# MCU.net
KiCad netlist of a schematic drawn in Altium Designer
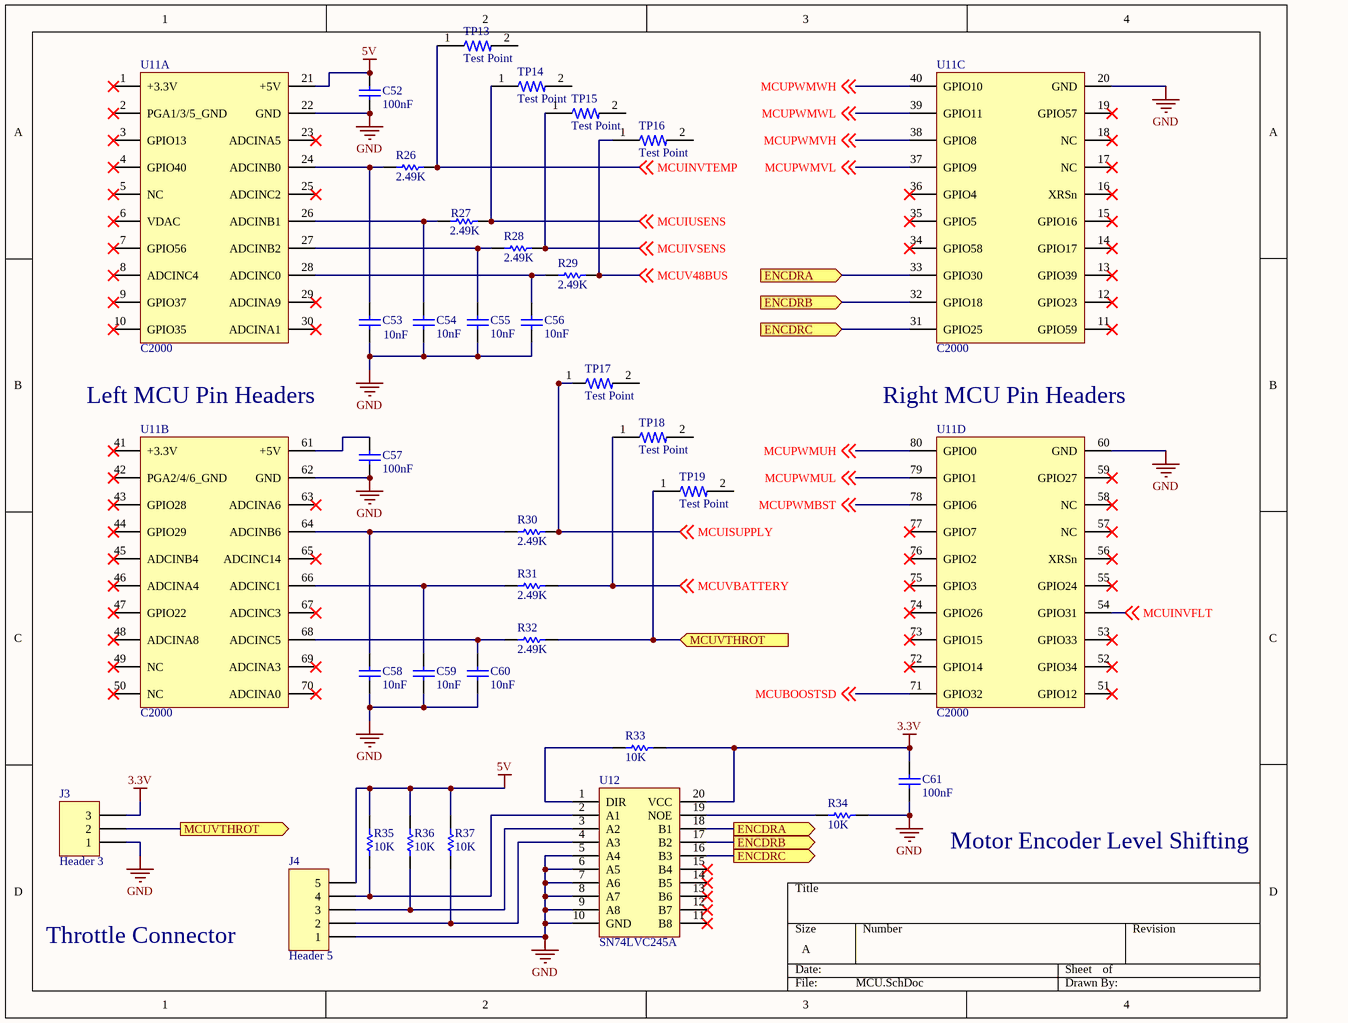
[diagram p0: MCU.SchDoc]

(export (version "E")
  (design (tool "Eeschema 10.0.6"))
  (components
    (comp (ref "C52")
      (value "100nF")
      (footprint "CAPC1609X100X15LL20")
      (fields
        (field (name "MANUFACTURER") "AVX Interconnect / Elco")
        (field (name "PART NUMBER") "TACL105M006XTA")
      )
      (libsource (lib "Altium Content Vault") (part "CAP"))
    )
    (comp (ref "C53")
      (value "10nF")
      (footprint "CAPC1609X100X15LL20")
      (fields
        (field (name "MANUFACTURER") "AVX Interconnect / Elco")
        (field (name "PART NUMBER") "TACL105M006XTA")
      )
      (libsource (lib "Altium Content Vault") (part "CAP"))
    )
    (comp (ref "C54")
      (value "10nF")
      (footprint "CAPC1609X100X15LL20")
      (fields
        (field (name "MANUFACTURER") "AVX Interconnect / Elco")
        (field (name "PART NUMBER") "TACL105M006XTA")
      )
      (libsource (lib "Altium Content Vault") (part "CAP"))
    )
    (comp (ref "C55")
      (value "10nF")
      (footprint "CAPC1609X100X15LL20")
      (fields
        (field (name "MANUFACTURER") "AVX Interconnect / Elco")
        (field (name "PART NUMBER") "TACL105M006XTA")
      )
      (libsource (lib "Altium Content Vault") (part "CAP"))
    )
    (comp (ref "C56")
      (value "10nF")
      (footprint "CAPC1609X100X15LL20")
      (fields
        (field (name "MANUFACTURER") "AVX Interconnect / Elco")
        (field (name "PART NUMBER") "TACL105M006XTA")
      )
      (libsource (lib "Altium Content Vault") (part "CAP"))
    )
    (comp (ref "C57")
      (value "100nF")
      (footprint "CAPC1609X100X15LL20")
      (fields
        (field (name "MANUFACTURER") "AVX Interconnect / Elco")
        (field (name "PART NUMBER") "TACL105M006XTA")
      )
      (libsource (lib "Altium Content Vault") (part "CAP"))
    )
    (comp (ref "C58")
      (value "10nF")
      (footprint "CAPC1609X100X15LL20")
      (fields
        (field (name "MANUFACTURER") "AVX Interconnect / Elco")
        (field (name "PART NUMBER") "TACL105M006XTA")
      )
      (libsource (lib "Altium Content Vault") (part "CAP"))
    )
    (comp (ref "C59")
      (value "10nF")
      (footprint "CAPC1609X100X15LL20")
      (fields
        (field (name "MANUFACTURER") "AVX Interconnect / Elco")
        (field (name "PART NUMBER") "TACL105M006XTA")
      )
      (libsource (lib "Altium Content Vault") (part "CAP"))
    )
    (comp (ref "C60")
      (value "10nF")
      (footprint "CAPC1609X100X15LL20")
      (fields
        (field (name "MANUFACTURER") "AVX Interconnect / Elco")
        (field (name "PART NUMBER") "TACL105M006XTA")
      )
      (libsource (lib "Altium Content Vault") (part "CAP"))
    )
    (comp (ref "C61")
      (value "100nF")
      (footprint "CAPC1609X100X15LL20")
      (fields
        (field (name "MANUFACTURER") "AVX Interconnect / Elco")
        (field (name "PART NUMBER") "TACL105M006XTA")
      )
      (libsource (lib "Altium Content Vault") (part "CAP"))
    )
    (comp (ref "J3")
      (value "Header 3")
      (footprint "3-Pin TB 5mm Pitch")
      (description "Header, 3-Pin")
      (fields (field (name "PUBLISHER") "Altium Limited"))
      (libsource (lib "Miscellaneous Connectors") (part "Header 3"))
    )
    (comp (ref "J4")
      (value "Header 5")
      (footprint "5-Pin TB 5mm Pitch")
      (description "Header, 5-Pin")
      (fields (field (name "PUBLISHER") "Altium Limited"))
      (libsource (lib "Miscellaneous Connectors") (part "Header 5"))
    )
    (comp (ref "R26")
      (value "2.49K")
      (footprint "RESC1609X50X30NL8T20")
      (description "Chip Resistor, 0 Ohm, Jumper, 100 mW, -55 to 155 degC, 0603 (1608 Metric), RoHS, Tape and Reel")
      (fields (field (name "MANUFACTURER") "Vishay Semiconductor"))
      (libsource (lib "Altium Content Vault") (part "RES-2"))
    )
    (comp (ref "R27")
      (value "2.49K")
      (footprint "RESC1609X50X30NL8T20")
      (description "Chip Resistor, 0 Ohm, Jumper, 100 mW, -55 to 155 degC, 0603 (1608 Metric), RoHS, Tape and Reel")
      (fields (field (name "MANUFACTURER") "Vishay Semiconductor"))
      (libsource (lib "Altium Content Vault") (part "RES-2"))
    )
    (comp (ref "R28")
      (value "2.49K")
      (footprint "RESC1609X50X30NL8T20")
      (description "Chip Resistor, 0 Ohm, Jumper, 100 mW, -55 to 155 degC, 0603 (1608 Metric), RoHS, Tape and Reel")
      (fields (field (name "MANUFACTURER") "Vishay Semiconductor"))
      (libsource (lib "Altium Content Vault") (part "RES-2"))
    )
    (comp (ref "R29")
      (value "2.49K")
      (footprint "RESC1609X50X30NL8T20")
      (description "Chip Resistor, 0 Ohm, Jumper, 100 mW, -55 to 155 degC, 0603 (1608 Metric), RoHS, Tape and Reel")
      (fields (field (name "MANUFACTURER") "Vishay Semiconductor"))
      (libsource (lib "Altium Content Vault") (part "RES-2"))
    )
    (comp (ref "R30")
      (value "2.49K")
      (footprint "RESC1609X50X30NL8T20")
      (description "Chip Resistor, 0 Ohm, Jumper, 100 mW, -55 to 155 degC, 0603 (1608 Metric), RoHS, Tape and Reel")
      (fields (field (name "MANUFACTURER") "Vishay Semiconductor"))
      (libsource (lib "Altium Content Vault") (part "RES-2"))
    )
    (comp (ref "R31")
      (value "2.49K")
      (footprint "RESC1609X50X30NL8T20")
      (description "Chip Resistor, 0 Ohm, Jumper, 100 mW, -55 to 155 degC, 0603 (1608 Metric), RoHS, Tape and Reel")
      (fields (field (name "MANUFACTURER") "Vishay Semiconductor"))
      (libsource (lib "Altium Content Vault") (part "RES-2"))
    )
    (comp (ref "R32")
      (value "2.49K")
      (footprint "RESC1609X50X30NL8T20")
      (description "Chip Resistor, 0 Ohm, Jumper, 100 mW, -55 to 155 degC, 0603 (1608 Metric), RoHS, Tape and Reel")
      (fields (field (name "MANUFACTURER") "Vishay Semiconductor"))
      (libsource (lib "Altium Content Vault") (part "RES-2"))
    )
    (comp (ref "R33")
      (value "10K")
      (footprint "RESC1609X50X30NL8T20")
      (description "Chip Resistor, 0 Ohm, Jumper, 100 mW, -55 to 155 degC, 0603 (1608 Metric), RoHS, Tape and Reel")
      (fields (field (name "MANUFACTURER") "Vishay Semiconductor"))
      (libsource (lib "Altium Content Vault") (part "RES-2"))
    )
    (comp (ref "R34")
      (value "10K")
      (footprint "RESC1609X50X30NL8T20")
      (description "Chip Resistor, 0 Ohm, Jumper, 100 mW, -55 to 155 degC, 0603 (1608 Metric), RoHS, Tape and Reel")
      (fields (field (name "MANUFACTURER") "Vishay Semiconductor"))
      (libsource (lib "Altium Content Vault") (part "RES-2"))
    )
    (comp (ref "R35")
      (value "10K")
      (footprint "RESC1609X50X30NL8T20")
      (description "Chip Resistor, 0 Ohm, Jumper, 100 mW, -55 to 155 degC, 0603 (1608 Metric), RoHS, Tape and Reel")
      (fields (field (name "MANUFACTURER") "Vishay Semiconductor"))
      (libsource (lib "Altium Content Vault") (part "RES-2"))
    )
    (comp (ref "R36")
      (value "10K")
      (footprint "RESC1609X50X30NL8T20")
      (description "Chip Resistor, 0 Ohm, Jumper, 100 mW, -55 to 155 degC, 0603 (1608 Metric), RoHS, Tape and Reel")
      (fields (field (name "MANUFACTURER") "Vishay Semiconductor"))
      (libsource (lib "Altium Content Vault") (part "RES-2"))
    )
    (comp (ref "R37")
      (value "10K")
      (footprint "RESC1609X50X30NL8T20")
      (description "Chip Resistor, 0 Ohm, Jumper, 100 mW, -55 to 155 degC, 0603 (1608 Metric), RoHS, Tape and Reel")
      (fields (field (name "MANUFACTURER") "Vishay Semiconductor"))
      (libsource (lib "Altium Content Vault") (part "RES-2"))
    )
    (comp (ref "TP13")
      (value "Test Point")
      (footprint "RESC3216X70N")
      (description "PC Test Point , Plating Surface Mount Mounting Type")
      (fields (field (name "MF") "KOA Speer") (field (name "MP") "RCWCTE"))
      (libsource (lib "SnapEDAsch") (part "RCWCTE"))
    )
    (comp (ref "TP14")
      (value "Test Point")
      (footprint "RESC3216X70N")
      (description "PC Test Point , Plating Surface Mount Mounting Type")
      (fields (field (name "MF") "KOA Speer") (field (name "MP") "RCWCTE"))
      (libsource (lib "SnapEDAsch") (part "RCWCTE"))
    )
    (comp (ref "TP15")
      (value "Test Point")
      (footprint "RESC3216X70N")
      (description "PC Test Point , Plating Surface Mount Mounting Type")
      (fields (field (name "MF") "KOA Speer") (field (name "MP") "RCWCTE"))
      (libsource (lib "SnapEDAsch") (part "RCWCTE"))
    )
    (comp (ref "TP16")
      (value "Test Point")
      (footprint "RESC3216X70N")
      (description "PC Test Point , Plating Surface Mount Mounting Type")
      (fields (field (name "MF") "KOA Speer") (field (name "MP") "RCWCTE"))
      (libsource (lib "SnapEDAsch") (part "RCWCTE"))
    )
    (comp (ref "TP17")
      (value "Test Point")
      (footprint "RESC3216X70N")
      (description "PC Test Point , Plating Surface Mount Mounting Type")
      (fields (field (name "MF") "KOA Speer") (field (name "MP") "RCWCTE"))
      (libsource (lib "SnapEDAsch") (part "RCWCTE"))
    )
    (comp (ref "TP18")
      (value "Test Point")
      (footprint "RESC3216X70N")
      (description "PC Test Point , Plating Surface Mount Mounting Type")
      (fields (field (name "MF") "KOA Speer") (field (name "MP") "RCWCTE"))
      (libsource (lib "SnapEDAsch") (part "RCWCTE"))
    )
    (comp (ref "TP19")
      (value "Test Point")
      (footprint "RESC3216X70N")
      (description "PC Test Point , Plating Surface Mount Mounting Type")
      (fields (field (name "MF") "KOA Speer") (field (name "MP") "RCWCTE"))
      (libsource (lib "SnapEDAsch") (part "RCWCTE"))
    )
    (comp (ref "U11")
      (value "C2000")
      (footprint "C2000")
      (description "F280049C")
      (libsource (lib "ee_453_yourname") (part "C2000"))
    )
    (comp (ref "U12")
      (value "SN74LVC245A")
      (footprint "20TSSOP")
      (description "Logic Level Transciever")
      (libsource (lib "ee_453_yourname") (part "SN74LVC245A"))
    )
  )
  (nets
    (net (code "1") (name "/ENCDRA") (class "Default")
      (node (ref "U11") (pin "33") (pinfunction "GPIO30_33") (pintype "passive"))
      (node (ref "U12") (pin "18") (pinfunction "B1_18") (pintype "passive"))
    )
    (net (code "2") (name "/ENCDRB") (class "Default")
      (node (ref "U11") (pin "32") (pinfunction "GPIO18_32") (pintype "passive"))
      (node (ref "U12") (pin "17") (pinfunction "B2_17") (pintype "passive"))
    )
    (net (code "3") (name "/ENCDRC") (class "Default")
      (node (ref "U11") (pin "31") (pinfunction "GPIO25_31") (pintype "passive"))
      (node (ref "U12") (pin "16") (pinfunction "B3_16") (pintype "passive"))
    )
    (net (code "4") (name "/MCUVTHROT") (class "Default")
      (node (ref "J3") (pin "2") (pinfunction "2_2") (pintype "passive"))
      (node (ref "R32") (pin "2") (pinfunction "2_2") (pintype "passive"))
      (node (ref "TP19") (pin "1") (pinfunction "1_1") (pintype "passive"))
    )
    (net (code "5") (name "3.3V") (class "Default")
      (node (ref "C61") (pin "2") (pinfunction "2_2") (pintype "passive"))
      (node (ref "J3") (pin "3") (pinfunction "3_3") (pintype "passive"))
      (node (ref "R33") (pin "2") (pinfunction "2_2") (pintype "passive"))
      (node (ref "U12") (pin "20") (pinfunction "VCC_20") (pintype "passive"))
    )
    (net (code "6") (name "5V") (class "Default")
      (node (ref "C52") (pin "2") (pinfunction "2_2") (pintype "passive"))
      (node (ref "J4") (pin "5") (pinfunction "5_5") (pintype "passive"))
      (node (ref "R35") (pin "2") (pinfunction "2_2") (pintype "passive"))
      (node (ref "R36") (pin "2") (pinfunction "2_2") (pintype "passive"))
      (node (ref "R37") (pin "2") (pinfunction "2_2") (pintype "passive"))
      (node (ref "U11") (pin "21") (pinfunction "+5V_21") (pintype "passive"))
    )
    (net (code "7") (name "GND") (class "Default")
      (node (ref "C52") (pin "1") (pinfunction "1_1") (pintype "passive"))
      (node (ref "C53") (pin "1") (pinfunction "1_1") (pintype "passive"))
      (node (ref "C54") (pin "1") (pinfunction "1_1") (pintype "passive"))
      (node (ref "C55") (pin "1") (pinfunction "1_1") (pintype "passive"))
      (node (ref "C56") (pin "1") (pinfunction "1_1") (pintype "passive"))
      (node (ref "C57") (pin "1") (pinfunction "1_1") (pintype "passive"))
      (node (ref "C58") (pin "1") (pinfunction "1_1") (pintype "passive"))
      (node (ref "C59") (pin "1") (pinfunction "1_1") (pintype "passive"))
      (node (ref "C60") (pin "1") (pinfunction "1_1") (pintype "passive"))
      (node (ref "C61") (pin "1") (pinfunction "1_1") (pintype "passive"))
      (node (ref "J3") (pin "1") (pinfunction "1_1") (pintype "passive"))
      (node (ref "J4") (pin "1") (pinfunction "1_1") (pintype "passive"))
      (node (ref "R34") (pin "2") (pinfunction "2_2") (pintype "passive"))
      (node (ref "U11") (pin "20") (pinfunction "GND_20") (pintype "passive"))
      (node (ref "U11") (pin "22") (pinfunction "GND_22") (pintype "passive"))
      (node (ref "U11") (pin "60") (pinfunction "GND_60") (pintype "passive"))
      (node (ref "U11") (pin "62") (pinfunction "GND_62") (pintype "passive"))
      (node (ref "U12") (pin "10") (pinfunction "GND_10") (pintype "passive"))
      (node (ref "U12") (pin "5") (pinfunction "A4_5") (pintype "passive"))
      (node (ref "U12") (pin "6") (pinfunction "A5_6") (pintype "passive"))
      (node (ref "U12") (pin "7") (pinfunction "A6_7") (pintype "passive"))
      (node (ref "U12") (pin "8") (pinfunction "A7_8") (pintype "passive"))
      (node (ref "U12") (pin "9") (pinfunction "A8_9") (pintype "passive"))
    )
    (net (code "8") (name "MCUBOOSTSD") (class "Default")
      (node (ref "U11") (pin "71") (pinfunction "GPIO32_71") (pintype "passive"))
    )
    (net (code "9") (name "MCUINVFLT") (class "Default")
      (node (ref "U11") (pin "54") (pinfunction "GPIO31_54") (pintype "passive"))
    )
    (net (code "10") (name "MCUINVTEMP") (class "Default")
      (node (ref "R26") (pin "2") (pinfunction "2_2") (pintype "passive"))
      (node (ref "TP13") (pin "1") (pinfunction "1_1") (pintype "passive"))
    )
    (net (code "11") (name "MCUISUPPLY") (class "Default")
      (node (ref "R30") (pin "2") (pinfunction "2_2") (pintype "passive"))
      (node (ref "TP17") (pin "1") (pinfunction "1_1") (pintype "passive"))
    )
    (net (code "12") (name "MCUIUSENS") (class "Default")
      (node (ref "R27") (pin "2") (pinfunction "2_2") (pintype "passive"))
      (node (ref "TP14") (pin "1") (pinfunction "1_1") (pintype "passive"))
    )
    (net (code "13") (name "MCUIVSENS") (class "Default")
      (node (ref "R28") (pin "2") (pinfunction "2_2") (pintype "passive"))
      (node (ref "TP15") (pin "1") (pinfunction "1_1") (pintype "passive"))
    )
    (net (code "14") (name "MCUPWMBST") (class "Default")
      (node (ref "U11") (pin "78") (pinfunction "GPIO6_78") (pintype "passive"))
    )
    (net (code "15") (name "MCUPWMUH") (class "Default")
      (node (ref "U11") (pin "80") (pinfunction "GPIO0_80") (pintype "passive"))
    )
    (net (code "16") (name "MCUPWMUL") (class "Default")
      (node (ref "U11") (pin "79") (pinfunction "GPIO1_79") (pintype "passive"))
    )
    (net (code "17") (name "MCUPWMVH") (class "Default")
      (node (ref "U11") (pin "38") (pinfunction "GPIO8_38") (pintype "passive"))
    )
    (net (code "18") (name "MCUPWMVL") (class "Default")
      (node (ref "U11") (pin "37") (pinfunction "GPIO9_37") (pintype "passive"))
    )
    (net (code "19") (name "MCUPWMWH") (class "Default")
      (node (ref "U11") (pin "40") (pinfunction "GPIO10_40") (pintype "passive"))
    )
    (net (code "20") (name "MCUPWMWL") (class "Default")
      (node (ref "U11") (pin "39") (pinfunction "GPIO11_39") (pintype "passive"))
    )
    (net (code "21") (name "MCUV48BUS") (class "Default")
      (node (ref "R29") (pin "2") (pinfunction "2_2") (pintype "passive"))
      (node (ref "TP16") (pin "1") (pinfunction "1_1") (pintype "passive"))
    )
    (net (code "22") (name "MCUVBATTERY") (class "Default")
      (node (ref "R31") (pin "2") (pinfunction "2_2") (pintype "passive"))
      (node (ref "TP18") (pin "1") (pinfunction "1_1") (pintype "passive"))
    )
    (net (code "23") (name "Net-(U11A-ADCINB0)") (class "Default")
      (node (ref "C53") (pin "2") (pinfunction "2_2") (pintype "passive"))
      (node (ref "R26") (pin "1") (pinfunction "1_1") (pintype "passive"))
      (node (ref "U11") (pin "24") (pinfunction "ADCINB0_24") (pintype "passive"))
    )
    (net (code "24") (name "Net-(U11A-ADCINB1)") (class "Default")
      (node (ref "C54") (pin "2") (pinfunction "2_2") (pintype "passive"))
      (node (ref "R27") (pin "1") (pinfunction "1_1") (pintype "passive"))
      (node (ref "U11") (pin "26") (pinfunction "ADCINB1_26") (pintype "passive"))
    )
    (net (code "25") (name "Net-(U11A-ADCINB2)") (class "Default")
      (node (ref "C55") (pin "2") (pinfunction "2_2") (pintype "passive"))
      (node (ref "R28") (pin "1") (pinfunction "1_1") (pintype "passive"))
      (node (ref "U11") (pin "27") (pinfunction "ADCINB2_27") (pintype "passive"))
    )
    (net (code "26") (name "Net-(U11A-ADCINC0)") (class "Default")
      (node (ref "C56") (pin "2") (pinfunction "2_2") (pintype "passive"))
      (node (ref "R29") (pin "1") (pinfunction "1_1") (pintype "passive"))
      (node (ref "U11") (pin "28") (pinfunction "ADCINC0_28") (pintype "passive"))
    )
    (net (code "27") (name "Net-(U11B-+5V)") (class "Default")
      (node (ref "C57") (pin "2") (pinfunction "2_2") (pintype "passive"))
      (node (ref "U11") (pin "61") (pinfunction "+5V_61") (pintype "passive"))
    )
    (net (code "28") (name "Net-(U11B-ADCINB6)") (class "Default")
      (node (ref "C58") (pin "2") (pinfunction "2_2") (pintype "passive"))
      (node (ref "R30") (pin "1") (pinfunction "1_1") (pintype "passive"))
      (node (ref "U11") (pin "64") (pinfunction "ADCINB6_64") (pintype "passive"))
    )
    (net (code "29") (name "Net-(U11B-ADCINC1)") (class "Default")
      (node (ref "C59") (pin "2") (pinfunction "2_2") (pintype "passive"))
      (node (ref "R31") (pin "1") (pinfunction "1_1") (pintype "passive"))
      (node (ref "U11") (pin "66") (pinfunction "ADCINC1_66") (pintype "passive"))
    )
    (net (code "30") (name "Net-(U11B-ADCINC5)") (class "Default")
      (node (ref "C60") (pin "2") (pinfunction "2_2") (pintype "passive"))
      (node (ref "R32") (pin "1") (pinfunction "1_1") (pintype "passive"))
      (node (ref "U11") (pin "68") (pinfunction "ADCINC5_68") (pintype "passive"))
    )
    (net (code "31") (name "Net-(U12-A1)") (class "Default")
      (node (ref "J4") (pin "4") (pinfunction "4_4") (pintype "passive"))
      (node (ref "R35") (pin "1") (pinfunction "1_1") (pintype "passive"))
      (node (ref "U12") (pin "2") (pinfunction "A1_2") (pintype "passive"))
    )
    (net (code "32") (name "Net-(U12-A2)") (class "Default")
      (node (ref "J4") (pin "3") (pinfunction "3_3") (pintype "passive"))
      (node (ref "R36") (pin "1") (pinfunction "1_1") (pintype "passive"))
      (node (ref "U12") (pin "3") (pinfunction "A2_3") (pintype "passive"))
    )
    (net (code "33") (name "Net-(U12-A3)") (class "Default")
      (node (ref "J4") (pin "2") (pinfunction "2_2") (pintype "passive"))
      (node (ref "R37") (pin "1") (pinfunction "1_1") (pintype "passive"))
      (node (ref "U12") (pin "4") (pinfunction "A3_4") (pintype "passive"))
    )
    (net (code "34") (name "Net-(U12-DIR)") (class "Default")
      (node (ref "R33") (pin "1") (pinfunction "1_1") (pintype "passive"))
      (node (ref "U12") (pin "1") (pinfunction "DIR_1") (pintype "passive"))
    )
    (net (code "35") (name "Net-(U12-NOE)") (class "Default")
      (node (ref "R34") (pin "1") (pinfunction "1_1") (pintype "passive"))
      (node (ref "U12") (pin "19") (pinfunction "NOE_19") (pintype "passive"))
    )
    (net (code "36") (name "unconnected-(TP13-Pad2)") (class "Default")
      (node (ref "TP13") (pin "2") (pinfunction "2_2") (pintype "passive"))
    )
    (net (code "37") (name "unconnected-(TP14-Pad2)") (class "Default")
      (node (ref "TP14") (pin "2") (pinfunction "2_2") (pintype "passive"))
    )
    (net (code "38") (name "unconnected-(TP15-Pad2)") (class "Default")
      (node (ref "TP15") (pin "2") (pinfunction "2_2") (pintype "passive"))
    )
    (net (code "39") (name "unconnected-(TP16-Pad2)") (class "Default")
      (node (ref "TP16") (pin "2") (pinfunction "2_2") (pintype "passive"))
    )
    (net (code "40") (name "unconnected-(TP17-Pad2)") (class "Default")
      (node (ref "TP17") (pin "2") (pinfunction "2_2") (pintype "passive"))
    )
    (net (code "41") (name "unconnected-(TP18-Pad2)") (class "Default")
      (node (ref "TP18") (pin "2") (pinfunction "2_2") (pintype "passive"))
    )
    (net (code "42") (name "unconnected-(TP19-Pad2)") (class "Default")
      (node (ref "TP19") (pin "2") (pinfunction "2_2") (pintype "passive"))
    )
    (net (code "43") (name "unconnected-(U11A-+3.3V-Pad1)") (class "Default")
      (node (ref "U11") (pin "1") (pinfunction "+3.3V_1") (pintype "passive+no_connect"))
    )
    (net (code "44") (name "unconnected-(U11A-ADCINA1-Pad30)") (class "Default")
      (node (ref "U11") (pin "30") (pinfunction "ADCINA1_30") (pintype "passive+no_connect"))
    )
    (net (code "45") (name "unconnected-(U11A-ADCINA5-Pad23)") (class "Default")
      (node (ref "U11") (pin "23") (pinfunction "ADCINA5_23") (pintype "passive+no_connect"))
    )
    (net (code "46") (name "unconnected-(U11A-ADCINA9-Pad29)") (class "Default")
      (node (ref "U11") (pin "29") (pinfunction "ADCINA9_29") (pintype "passive+no_connect"))
    )
    (net (code "47") (name "unconnected-(U11A-ADCINC2-Pad25)") (class "Default")
      (node (ref "U11") (pin "25") (pinfunction "ADCINC2_25") (pintype "passive+no_connect"))
    )
    (net (code "48") (name "unconnected-(U11A-ADCINC4-Pad8)") (class "Default")
      (node (ref "U11") (pin "8") (pinfunction "ADCINC4_8") (pintype "passive+no_connect"))
    )
    (net (code "49") (name "unconnected-(U11A-GPIO13-Pad3)") (class "Default")
      (node (ref "U11") (pin "3") (pinfunction "GPIO13_3") (pintype "passive+no_connect"))
    )
    (net (code "50") (name "unconnected-(U11A-GPIO35-Pad10)") (class "Default")
      (node (ref "U11") (pin "10") (pinfunction "GPIO35_10") (pintype "passive+no_connect"))
    )
    (net (code "51") (name "unconnected-(U11A-GPIO37-Pad9)") (class "Default")
      (node (ref "U11") (pin "9") (pinfunction "GPIO37_9") (pintype "passive+no_connect"))
    )
    (net (code "52") (name "unconnected-(U11A-GPIO40-Pad4)") (class "Default")
      (node (ref "U11") (pin "4") (pinfunction "GPIO40_4") (pintype "passive+no_connect"))
    )
    (net (code "53") (name "unconnected-(U11A-GPIO56-Pad7)") (class "Default")
      (node (ref "U11") (pin "7") (pinfunction "GPIO56_7") (pintype "passive+no_connect"))
    )
    (net (code "54") (name "unconnected-(U11A-NC-Pad5)") (class "Default")
      (node (ref "U11") (pin "5") (pinfunction "NC_5") (pintype "passive+no_connect"))
    )
    (net (code "55") (name "unconnected-(U11A-PGA1{slash}3{slash}5_GND-Pad2)") (class "Default")
      (node (ref "U11") (pin "2") (pinfunction "PGA1/3/5_GND_2") (pintype "passive+no_connect"))
    )
    (net (code "56") (name "unconnected-(U11A-VDAC-Pad6)") (class "Default")
      (node (ref "U11") (pin "6") (pinfunction "VDAC_6") (pintype "passive+no_connect"))
    )
    (net (code "57") (name "unconnected-(U11B-+3.3V-Pad41)") (class "Default")
      (node (ref "U11") (pin "41") (pinfunction "+3.3V_41") (pintype "passive+no_connect"))
    )
    (net (code "58") (name "unconnected-(U11B-ADCINA0-Pad70)") (class "Default")
      (node (ref "U11") (pin "70") (pinfunction "ADCINA0_70") (pintype "passive+no_connect"))
    )
    (net (code "59") (name "unconnected-(U11B-ADCINA3-Pad69)") (class "Default")
      (node (ref "U11") (pin "69") (pinfunction "ADCINA3_69") (pintype "passive+no_connect"))
    )
    (net (code "60") (name "unconnected-(U11B-ADCINA4-Pad46)") (class "Default")
      (node (ref "U11") (pin "46") (pinfunction "ADCINA4_46") (pintype "passive+no_connect"))
    )
    (net (code "61") (name "unconnected-(U11B-ADCINA6-Pad63)") (class "Default")
      (node (ref "U11") (pin "63") (pinfunction "ADCINA6_63") (pintype "passive+no_connect"))
    )
    (net (code "62") (name "unconnected-(U11B-ADCINA8-Pad48)") (class "Default")
      (node (ref "U11") (pin "48") (pinfunction "ADCINA8_48") (pintype "passive+no_connect"))
    )
    (net (code "63") (name "unconnected-(U11B-ADCINB4-Pad45)") (class "Default")
      (node (ref "U11") (pin "45") (pinfunction "ADCINB4_45") (pintype "passive+no_connect"))
    )
    (net (code "64") (name "unconnected-(U11B-ADCINC3-Pad67)") (class "Default")
      (node (ref "U11") (pin "67") (pinfunction "ADCINC3_67") (pintype "passive+no_connect"))
    )
    (net (code "65") (name "unconnected-(U11B-ADCINC14-Pad65)") (class "Default")
      (node (ref "U11") (pin "65") (pinfunction "ADCINC14_65") (pintype "passive+no_connect"))
    )
    (net (code "66") (name "unconnected-(U11B-GPIO22-Pad47)") (class "Default")
      (node (ref "U11") (pin "47") (pinfunction "GPIO22_47") (pintype "passive+no_connect"))
    )
    (net (code "67") (name "unconnected-(U11B-GPIO28-Pad43)") (class "Default")
      (node (ref "U11") (pin "43") (pinfunction "GPIO28_43") (pintype "passive+no_connect"))
    )
    (net (code "68") (name "unconnected-(U11B-GPIO29-Pad44)") (class "Default")
      (node (ref "U11") (pin "44") (pinfunction "GPIO29_44") (pintype "passive+no_connect"))
    )
    (net (code "69") (name "unconnected-(U11B-NC-Pad49)") (class "Default")
      (node (ref "U11") (pin "49") (pinfunction "NC_49") (pintype "passive+no_connect"))
    )
    (net (code "70") (name "unconnected-(U11B-NC-Pad50)") (class "Default")
      (node (ref "U11") (pin "50") (pinfunction "NC_50") (pintype "passive+no_connect"))
    )
    (net (code "71") (name "unconnected-(U11B-PGA2{slash}4{slash}6_GND-Pad42)") (class "Default")
      (node (ref "U11") (pin "42") (pinfunction "PGA2/4/6_GND_42") (pintype "passive+no_connect"))
    )
    (net (code "72") (name "unconnected-(U11C-GPIO4-Pad36)") (class "Default")
      (node (ref "U11") (pin "36") (pinfunction "GPIO4_36") (pintype "passive+no_connect"))
    )
    (net (code "73") (name "unconnected-(U11C-GPIO5-Pad35)") (class "Default")
      (node (ref "U11") (pin "35") (pinfunction "GPIO5_35") (pintype "passive+no_connect"))
    )
    (net (code "74") (name "unconnected-(U11C-GPIO16-Pad15)") (class "Default")
      (node (ref "U11") (pin "15") (pinfunction "GPIO16_15") (pintype "passive+no_connect"))
    )
    (net (code "75") (name "unconnected-(U11C-GPIO17-Pad14)") (class "Default")
      (node (ref "U11") (pin "14") (pinfunction "GPIO17_14") (pintype "passive+no_connect"))
    )
    (net (code "76") (name "unconnected-(U11C-GPIO23-Pad12)") (class "Default")
      (node (ref "U11") (pin "12") (pinfunction "GPIO23_12") (pintype "passive+no_connect"))
    )
    (net (code "77") (name "unconnected-(U11C-GPIO39-Pad13)") (class "Default")
      (node (ref "U11") (pin "13") (pinfunction "GPIO39_13") (pintype "passive+no_connect"))
    )
    (net (code "78") (name "unconnected-(U11C-GPIO57-Pad19)") (class "Default")
      (node (ref "U11") (pin "19") (pinfunction "GPIO57_19") (pintype "passive+no_connect"))
    )
    (net (code "79") (name "unconnected-(U11C-GPIO58-Pad34)") (class "Default")
      (node (ref "U11") (pin "34") (pinfunction "GPIO58_34") (pintype "passive+no_connect"))
    )
    (net (code "80") (name "unconnected-(U11C-GPIO59-Pad11)") (class "Default")
      (node (ref "U11") (pin "11") (pinfunction "GPIO59_11") (pintype "passive+no_connect"))
    )
    (net (code "81") (name "unconnected-(U11C-NC-Pad17)") (class "Default")
      (node (ref "U11") (pin "17") (pinfunction "NC_17") (pintype "passive+no_connect"))
    )
    (net (code "82") (name "unconnected-(U11C-NC-Pad18)") (class "Default")
      (node (ref "U11") (pin "18") (pinfunction "NC_18") (pintype "passive+no_connect"))
    )
    (net (code "83") (name "unconnected-(U11C-XRSn-Pad16)") (class "Default")
      (node (ref "U11") (pin "16") (pinfunction "XRSn_16") (pintype "passive+no_connect"))
    )
    (net (code "84") (name "unconnected-(U11D-GPIO2-Pad76)") (class "Default")
      (node (ref "U11") (pin "76") (pinfunction "GPIO2_76") (pintype "passive+no_connect"))
    )
    (net (code "85") (name "unconnected-(U11D-GPIO3-Pad75)") (class "Default")
      (node (ref "U11") (pin "75") (pinfunction "GPIO3_75") (pintype "passive+no_connect"))
    )
    (net (code "86") (name "unconnected-(U11D-GPIO7-Pad77)") (class "Default")
      (node (ref "U11") (pin "77") (pinfunction "GPIO7_77") (pintype "passive+no_connect"))
    )
    (net (code "87") (name "unconnected-(U11D-GPIO12-Pad51)") (class "Default")
      (node (ref "U11") (pin "51") (pinfunction "GPIO12_51") (pintype "passive+no_connect"))
    )
    (net (code "88") (name "unconnected-(U11D-GPIO14-Pad72)") (class "Default")
      (node (ref "U11") (pin "72") (pinfunction "GPIO14_72") (pintype "passive+no_connect"))
    )
    (net (code "89") (name "unconnected-(U11D-GPIO15-Pad73)") (class "Default")
      (node (ref "U11") (pin "73") (pinfunction "GPIO15_73") (pintype "passive+no_connect"))
    )
    (net (code "90") (name "unconnected-(U11D-GPIO24-Pad55)") (class "Default")
      (node (ref "U11") (pin "55") (pinfunction "GPIO24_55") (pintype "passive+no_connect"))
    )
    (net (code "91") (name "unconnected-(U11D-GPIO26-Pad74)") (class "Default")
      (node (ref "U11") (pin "74") (pinfunction "GPIO26_74") (pintype "passive+no_connect"))
    )
    (net (code "92") (name "unconnected-(U11D-GPIO27-Pad59)") (class "Default")
      (node (ref "U11") (pin "59") (pinfunction "GPIO27_59") (pintype "passive+no_connect"))
    )
    (net (code "93") (name "unconnected-(U11D-GPIO33-Pad53)") (class "Default")
      (node (ref "U11") (pin "53") (pinfunction "GPIO33_53") (pintype "passive+no_connect"))
    )
    (net (code "94") (name "unconnected-(U11D-GPIO34-Pad52)") (class "Default")
      (node (ref "U11") (pin "52") (pinfunction "GPIO34_52") (pintype "passive+no_connect"))
    )
    (net (code "95") (name "unconnected-(U11D-NC-Pad57)") (class "Default")
      (node (ref "U11") (pin "57") (pinfunction "NC_57") (pintype "passive+no_connect"))
    )
    (net (code "96") (name "unconnected-(U11D-NC-Pad58)") (class "Default")
      (node (ref "U11") (pin "58") (pinfunction "NC_58") (pintype "passive+no_connect"))
    )
    (net (code "97") (name "unconnected-(U11D-XRSn-Pad56)") (class "Default")
      (node (ref "U11") (pin "56") (pinfunction "XRSn_56") (pintype "passive+no_connect"))
    )
    (net (code "98") (name "unconnected-(U12-B4-Pad15)") (class "Default")
      (node (ref "U12") (pin "15") (pinfunction "B4_15") (pintype "passive+no_connect"))
    )
    (net (code "99") (name "unconnected-(U12-B5-Pad14)") (class "Default")
      (node (ref "U12") (pin "14") (pinfunction "B5_14") (pintype "passive+no_connect"))
    )
    (net (code "100") (name "unconnected-(U12-B6-Pad13)") (class "Default")
      (node (ref "U12") (pin "13") (pinfunction "B6_13") (pintype "passive+no_connect"))
    )
    (net (code "101") (name "unconnected-(U12-B7-Pad12)") (class "Default")
      (node (ref "U12") (pin "12") (pinfunction "B7_12") (pintype "passive+no_connect"))
    )
    (net (code "102") (name "unconnected-(U12-B8-Pad11)") (class "Default")
      (node (ref "U12") (pin "11") (pinfunction "B8_11") (pintype "passive+no_connect"))
    )
  )
)
